# Sheet1.net
KiCad netlist of a schematic drawn in Altium Designer
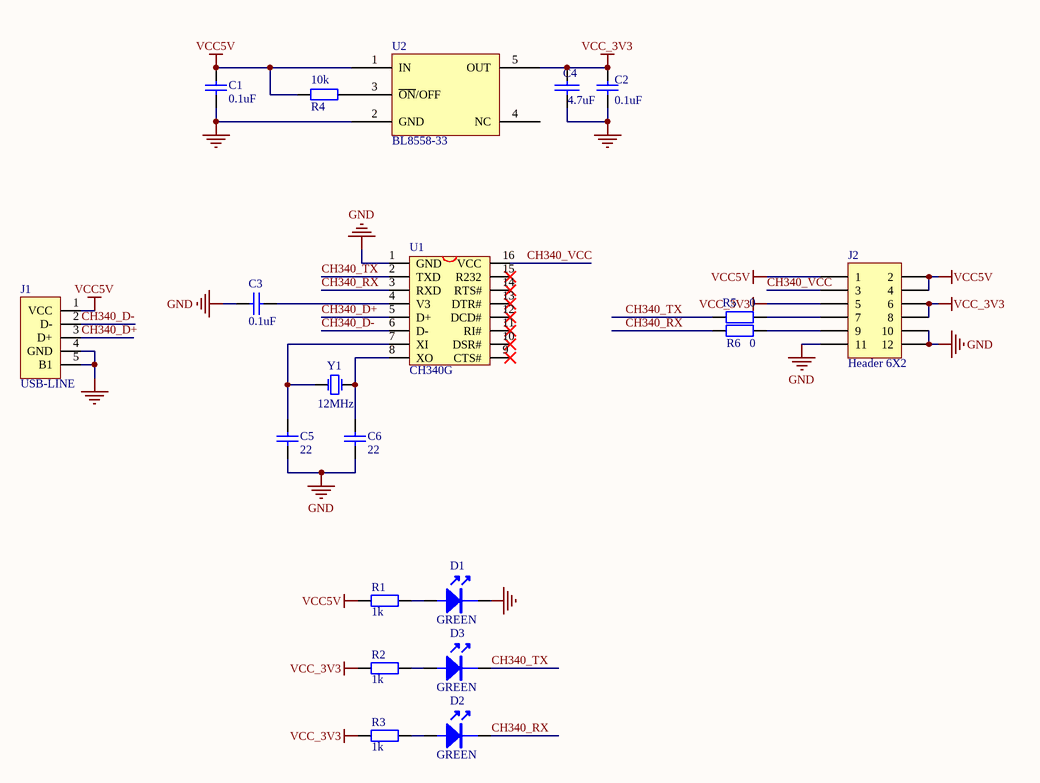
[diagram p0: Sheet1.SchDoc]

(export (version "E")
  (design (tool "Eeschema 10.0.6"))
  (components
    (comp (ref "C1")
      (value "0.1uF")
      (footprint "FT_0603 - C_3D")
      (description "CAP CER .1UF 16V 10% X7R 0603")
      (fields
        (field (name "PART NUMBER") "GRM188R71C104KA01D")
        (field (name "MANUFACTURER") "Murata Electronics North America")
      )
      (libsource (lib "Altium_SVN_Library") (part "Capacitor"))
    )
    (comp (ref "C2")
      (value "0.1uF")
      (footprint "FT_0603 - C_3D")
      (description "CAP CER .1UF 16V 10% X7R 0603")
      (fields
        (field (name "PART NUMBER") "GRM188R71C104KA01D")
        (field (name "MANUFACTURER") "Murata Electronics North America")
      )
      (libsource (lib "Altium_SVN_Library") (part "Capacitor"))
    )
    (comp (ref "C3")
      (value "0.1uF")
      (footprint "FT_0603 - C_3D")
      (description "CAP CER .1UF 16V 10% X7R 0603")
      (fields
        (field (name "PART NUMBER") "GRM188R71C104KA01D")
        (field (name "MANUFACTURER") "Murata Electronics North America")
      )
      (libsource (lib "Altium_SVN_Library") (part "Capacitor"))
    )
    (comp (ref "C4")
      (value "4.7uF")
      (footprint "FT_0805_C")
      (description "Capacitor")
      (libsource (lib "*") (part "CAP"))
    )
    (comp (ref "C5")
      (value "22")
      (footprint "FT_0603 - C_3D")
      (description "Capacitor")
      (fields (field (name "PUBLISHER") "Altium Limited"))
      (libsource (lib "*") (part "Cap"))
    )
    (comp (ref "C6")
      (value "22")
      (footprint "FT_0603 - C_3D")
      (description "Capacitor")
      (fields (field (name "PUBLISHER") "Altium Limited"))
      (libsource (lib "*") (part "Cap"))
    )
    (comp (ref "D1") (value "GREEN") (footprint "FT_0603_D") (libsource (lib "FTSCH") (part "LED")))
    (comp (ref "D2") (value "GREEN") (footprint "FT_0603_D") (libsource (lib "FTSCH") (part "LED")))
    (comp (ref "D3") (value "GREEN") (footprint "FT_0603_D") (libsource (lib "FTSCH") (part "LED")))
    (comp (ref "J1")
      (value "USB-LINE")
      (footprint "FT_USBIF_Micro_BT_CB")
      (libsource (lib "USB转TTL") (part "USB-LINE"))
    )
    (comp (ref "J2")
      (value "Header 6X2")
      (footprint "HDR2X6")
      (description "Header, 6-Pin, Dual row")
      (fields (field (name "PUBLISHER") "Altium Limited"))
      (libsource (lib "Miscellaneous Connectors") (part "Header 6X2"))
    )
    (comp (ref "R1")
      (value "1k")
      (footprint "0603P")
      (description "RES 1.0M OHM 1/10W 5% 0603 SMD")
      (fields (field (name "PART NUMBER") "RC0603JR-071ML") (field (name "MANUFACTURER") "Yageo"))
      (libsource (lib "*") (part "Resistor"))
    )
    (comp (ref "R2")
      (value "1k")
      (footprint "0603P")
      (description "RES 1.0M OHM 1/10W 5% 0603 SMD")
      (fields (field (name "PART NUMBER") "RC0603JR-071ML") (field (name "MANUFACTURER") "Yageo"))
      (libsource (lib "*") (part "Resistor"))
    )
    (comp (ref "R3")
      (value "1k")
      (footprint "0603P")
      (description "RES 1.0M OHM 1/10W 5% 0603 SMD")
      (fields (field (name "PART NUMBER") "RC0603JR-071ML") (field (name "MANUFACTURER") "Yageo"))
      (libsource (lib "*") (part "Resistor"))
    )
    (comp (ref "R4")
      (value "10k")
      (footprint "0603P")
      (description "RES 1.0M OHM 1/10W 5% 0603 SMD")
      (fields (field (name "PART NUMBER") "RC0603JR-071ML") (field (name "MANUFACTURER") "Yageo"))
      (libsource (lib "*") (part "Resistor"))
    )
    (comp (ref "R5")
      (value "0")
      (footprint "0603P")
      (description "RES 1.0M OHM 1/10W 5% 0603 SMD")
      (fields (field (name "PART NUMBER") "RC0603JR-071ML") (field (name "MANUFACTURER") "Yageo"))
      (libsource (lib "*") (part "Resistor"))
    )
    (comp (ref "R6")
      (value "0")
      (footprint "0603P")
      (description "RES 1.0M OHM 1/10W 5% 0603 SMD")
      (fields (field (name "PART NUMBER") "RC0603JR-071ML") (field (name "MANUFACTURER") "Yageo"))
      (libsource (lib "*") (part "Resistor"))
    )
    (comp (ref "U1")
      (value "CH340G")
      (footprint "SOP16M")
      (description "USB2UART")
      (libsource (lib "WARSHIP") (part "CH340G"))
    )
    (comp (ref "U2") (value "BL8558-33") (footprint "FT_SOT-23-5") (libsource (lib "FTSCH") (part "LDO_5")))
    (comp (ref "Y1")
      (value "12MHz")
      (footprint "XTAL_US")
      (description "Crystal Oscillator")
      (fields (field (name "PUBLISHER") "Altium Limited"))
      (libsource (lib "战舰STM32开发板底板封装库") (part "XTAL_2"))
    )
  )
  (nets
    (net (code "1") (name "/CH340_D+") (class "Default")
      (node (ref "J1") (pin "3") (pinfunction "D+_3") (pintype "passive"))
      (node (ref "U1") (pin "5") (pinfunction "D+_5") (pintype "passive"))
    )
    (net (code "2") (name "/CH340_D-") (class "Default")
      (node (ref "J1") (pin "2") (pinfunction "D-_2") (pintype "passive"))
      (node (ref "U1") (pin "6") (pinfunction "D-_6") (pintype "passive"))
    )
    (net (code "3") (name "/CH340_RX") (class "Default")
      (node (ref "D2") (pin "2") (pinfunction "2_2") (pintype "passive"))
      (node (ref "R6") (pin "1") (pinfunction "1_1") (pintype "passive"))
      (node (ref "U1") (pin "3") (pinfunction "RXD_3") (pintype "passive"))
    )
    (net (code "4") (name "/CH340_TX") (class "Default")
      (node (ref "D3") (pin "2") (pinfunction "2_2") (pintype "passive"))
      (node (ref "R5") (pin "1") (pinfunction "1_1") (pintype "passive"))
      (node (ref "U1") (pin "2") (pinfunction "TXD_2") (pintype "passive"))
    )
    (net (code "5") (name "/CH340_VCC") (class "Default")
      (node (ref "J2") (pin "3") (pinfunction "3_3") (pintype "passive"))
      (node (ref "U1") (pin "16") (pinfunction "VCC_16") (pintype "passive"))
    )
    (net (code "6") (name "GND") (class "Default")
      (node (ref "C1") (pin "1") (pinfunction "1_1") (pintype "passive"))
      (node (ref "C2") (pin "1") (pinfunction "1_1") (pintype "passive"))
      (node (ref "C3") (pin "2") (pinfunction "2_2") (pintype "passive"))
      (node (ref "C4") (pin "1") (pinfunction "1_1") (pintype "passive"))
      (node (ref "C5") (pin "2") (pinfunction "2_2") (pintype "passive"))
      (node (ref "C6") (pin "2") (pinfunction "2_2") (pintype "passive"))
      (node (ref "D1") (pin "2") (pinfunction "2_2") (pintype "passive"))
      (node (ref "J1") (pin "4") (pinfunction "GND_4") (pintype "passive"))
      (node (ref "J1") (pin "5") (pinfunction "B1_5") (pintype "passive"))
      (node (ref "J2") (pin "10") (pinfunction "10_10") (pintype "passive"))
      (node (ref "J2") (pin "11") (pinfunction "11_11") (pintype "passive"))
      (node (ref "J2") (pin "12") (pinfunction "12_12") (pintype "passive"))
      (node (ref "U1") (pin "1") (pinfunction "GND_1") (pintype "passive"))
      (node (ref "U2") (pin "2") (pinfunction "GND_2") (pintype "power_in"))
    )
    (net (code "7") (name "Net-(D1-Pad1)") (class "Default")
      (node (ref "D1") (pin "1") (pinfunction "1_1") (pintype "passive"))
      (node (ref "R1") (pin "2") (pinfunction "2_2") (pintype "passive"))
    )
    (net (code "8") (name "Net-(D2-Pad1)") (class "Default")
      (node (ref "D2") (pin "1") (pinfunction "1_1") (pintype "passive"))
      (node (ref "R3") (pin "2") (pinfunction "2_2") (pintype "passive"))
    )
    (net (code "9") (name "Net-(D3-Pad1)") (class "Default")
      (node (ref "D3") (pin "1") (pinfunction "1_1") (pintype "passive"))
      (node (ref "R2") (pin "2") (pinfunction "2_2") (pintype "passive"))
    )
    (net (code "10") (name "Net-(J2-Pad7)") (class "Default")
      (node (ref "J2") (pin "7") (pinfunction "7_7") (pintype "passive"))
      (node (ref "R5") (pin "2") (pinfunction "2_2") (pintype "passive"))
    )
    (net (code "11") (name "Net-(J2-Pad9)") (class "Default")
      (node (ref "J2") (pin "9") (pinfunction "9_9") (pintype "passive"))
      (node (ref "R6") (pin "2") (pinfunction "2_2") (pintype "passive"))
    )
    (net (code "12") (name "Net-(U1-V3)") (class "Default")
      (node (ref "C3") (pin "1") (pinfunction "1_1") (pintype "passive"))
      (node (ref "U1") (pin "4") (pinfunction "V3_4") (pintype "passive"))
    )
    (net (code "13") (name "Net-(U1-XI)") (class "Default")
      (node (ref "C5") (pin "1") (pinfunction "1_1") (pintype "passive"))
      (node (ref "U1") (pin "7") (pinfunction "XI_7") (pintype "passive"))
      (node (ref "Y1") (pin "1") (pinfunction "OSC1_1") (pintype "passive"))
    )
    (net (code "14") (name "Net-(U1-XO)") (class "Default")
      (node (ref "C6") (pin "1") (pinfunction "1_1") (pintype "passive"))
      (node (ref "U1") (pin "8") (pinfunction "XO_8") (pintype "passive"))
      (node (ref "Y1") (pin "2") (pinfunction "OSC2_2") (pintype "passive"))
    )
    (net (code "15") (name "Net-(U2-~{ON}{slash}OFF)") (class "Default")
      (node (ref "R4") (pin "2") (pinfunction "2_2") (pintype "passive"))
      (node (ref "U2") (pin "3") (pinfunction "~{ON}/OFF_3") (pintype "passive"))
    )
    (net (code "16") (name "VCC5V") (class "Default")
      (node (ref "C1") (pin "2") (pinfunction "2_2") (pintype "passive"))
      (node (ref "J1") (pin "1") (pinfunction "VCC_1") (pintype "passive"))
      (node (ref "J2") (pin "1") (pinfunction "1_1") (pintype "passive"))
      (node (ref "J2") (pin "2") (pinfunction "2_2") (pintype "passive"))
      (node (ref "J2") (pin "4") (pinfunction "4_4") (pintype "passive"))
      (node (ref "R1") (pin "1") (pinfunction "1_1") (pintype "passive"))
      (node (ref "R4") (pin "1") (pinfunction "1_1") (pintype "passive"))
      (node (ref "U2") (pin "1") (pinfunction "IN_1") (pintype "power_in"))
    )
    (net (code "17") (name "VCC_3V3") (class "Default")
      (node (ref "C2") (pin "2") (pinfunction "2_2") (pintype "passive"))
      (node (ref "C4") (pin "2") (pinfunction "2_2") (pintype "passive"))
      (node (ref "J2") (pin "5") (pinfunction "5_5") (pintype "passive"))
      (node (ref "J2") (pin "6") (pinfunction "6_6") (pintype "passive"))
      (node (ref "J2") (pin "8") (pinfunction "8_8") (pintype "passive"))
      (node (ref "R2") (pin "1") (pinfunction "1_1") (pintype "passive"))
      (node (ref "R3") (pin "1") (pinfunction "1_1") (pintype "passive"))
      (node (ref "U2") (pin "5") (pinfunction "OUT_5") (pintype "power_in"))
    )
    (net (code "18") (name "unconnected-(U1-CTS#-Pad9)") (class "Default")
      (node (ref "U1") (pin "9") (pinfunction "CTS#_9") (pintype "passive+no_connect"))
    )
    (net (code "19") (name "unconnected-(U1-DCD#-Pad12)") (class "Default")
      (node (ref "U1") (pin "12") (pinfunction "DCD#_12") (pintype "passive+no_connect"))
    )
    (net (code "20") (name "unconnected-(U1-DSR#-Pad10)") (class "Default")
      (node (ref "U1") (pin "10") (pinfunction "DSR#_10") (pintype "passive+no_connect"))
    )
    (net (code "21") (name "unconnected-(U1-DTR#-Pad13)") (class "Default")
      (node (ref "U1") (pin "13") (pinfunction "DTR#_13") (pintype "passive+no_connect"))
    )
    (net (code "22") (name "unconnected-(U1-R232-Pad15)") (class "Default")
      (node (ref "U1") (pin "15") (pinfunction "R232_15") (pintype "passive+no_connect"))
    )
    (net (code "23") (name "unconnected-(U1-RI#-Pad11)") (class "Default")
      (node (ref "U1") (pin "11") (pinfunction "RI#_11") (pintype "passive+no_connect"))
    )
    (net (code "24") (name "unconnected-(U1-RTS#-Pad14)") (class "Default")
      (node (ref "U1") (pin "14") (pinfunction "RTS#_14") (pintype "passive+no_connect"))
    )
    (net (code "25") (name "unconnected-(U2-NC-Pad4)") (class "Default")
      (node (ref "U2") (pin "4") (pinfunction "NC_4") (pintype "passive"))
    )
  )
)
